# 5_ButtonsAndLEDs.net
KiCad netlist of a schematic drawn in Altium Designer
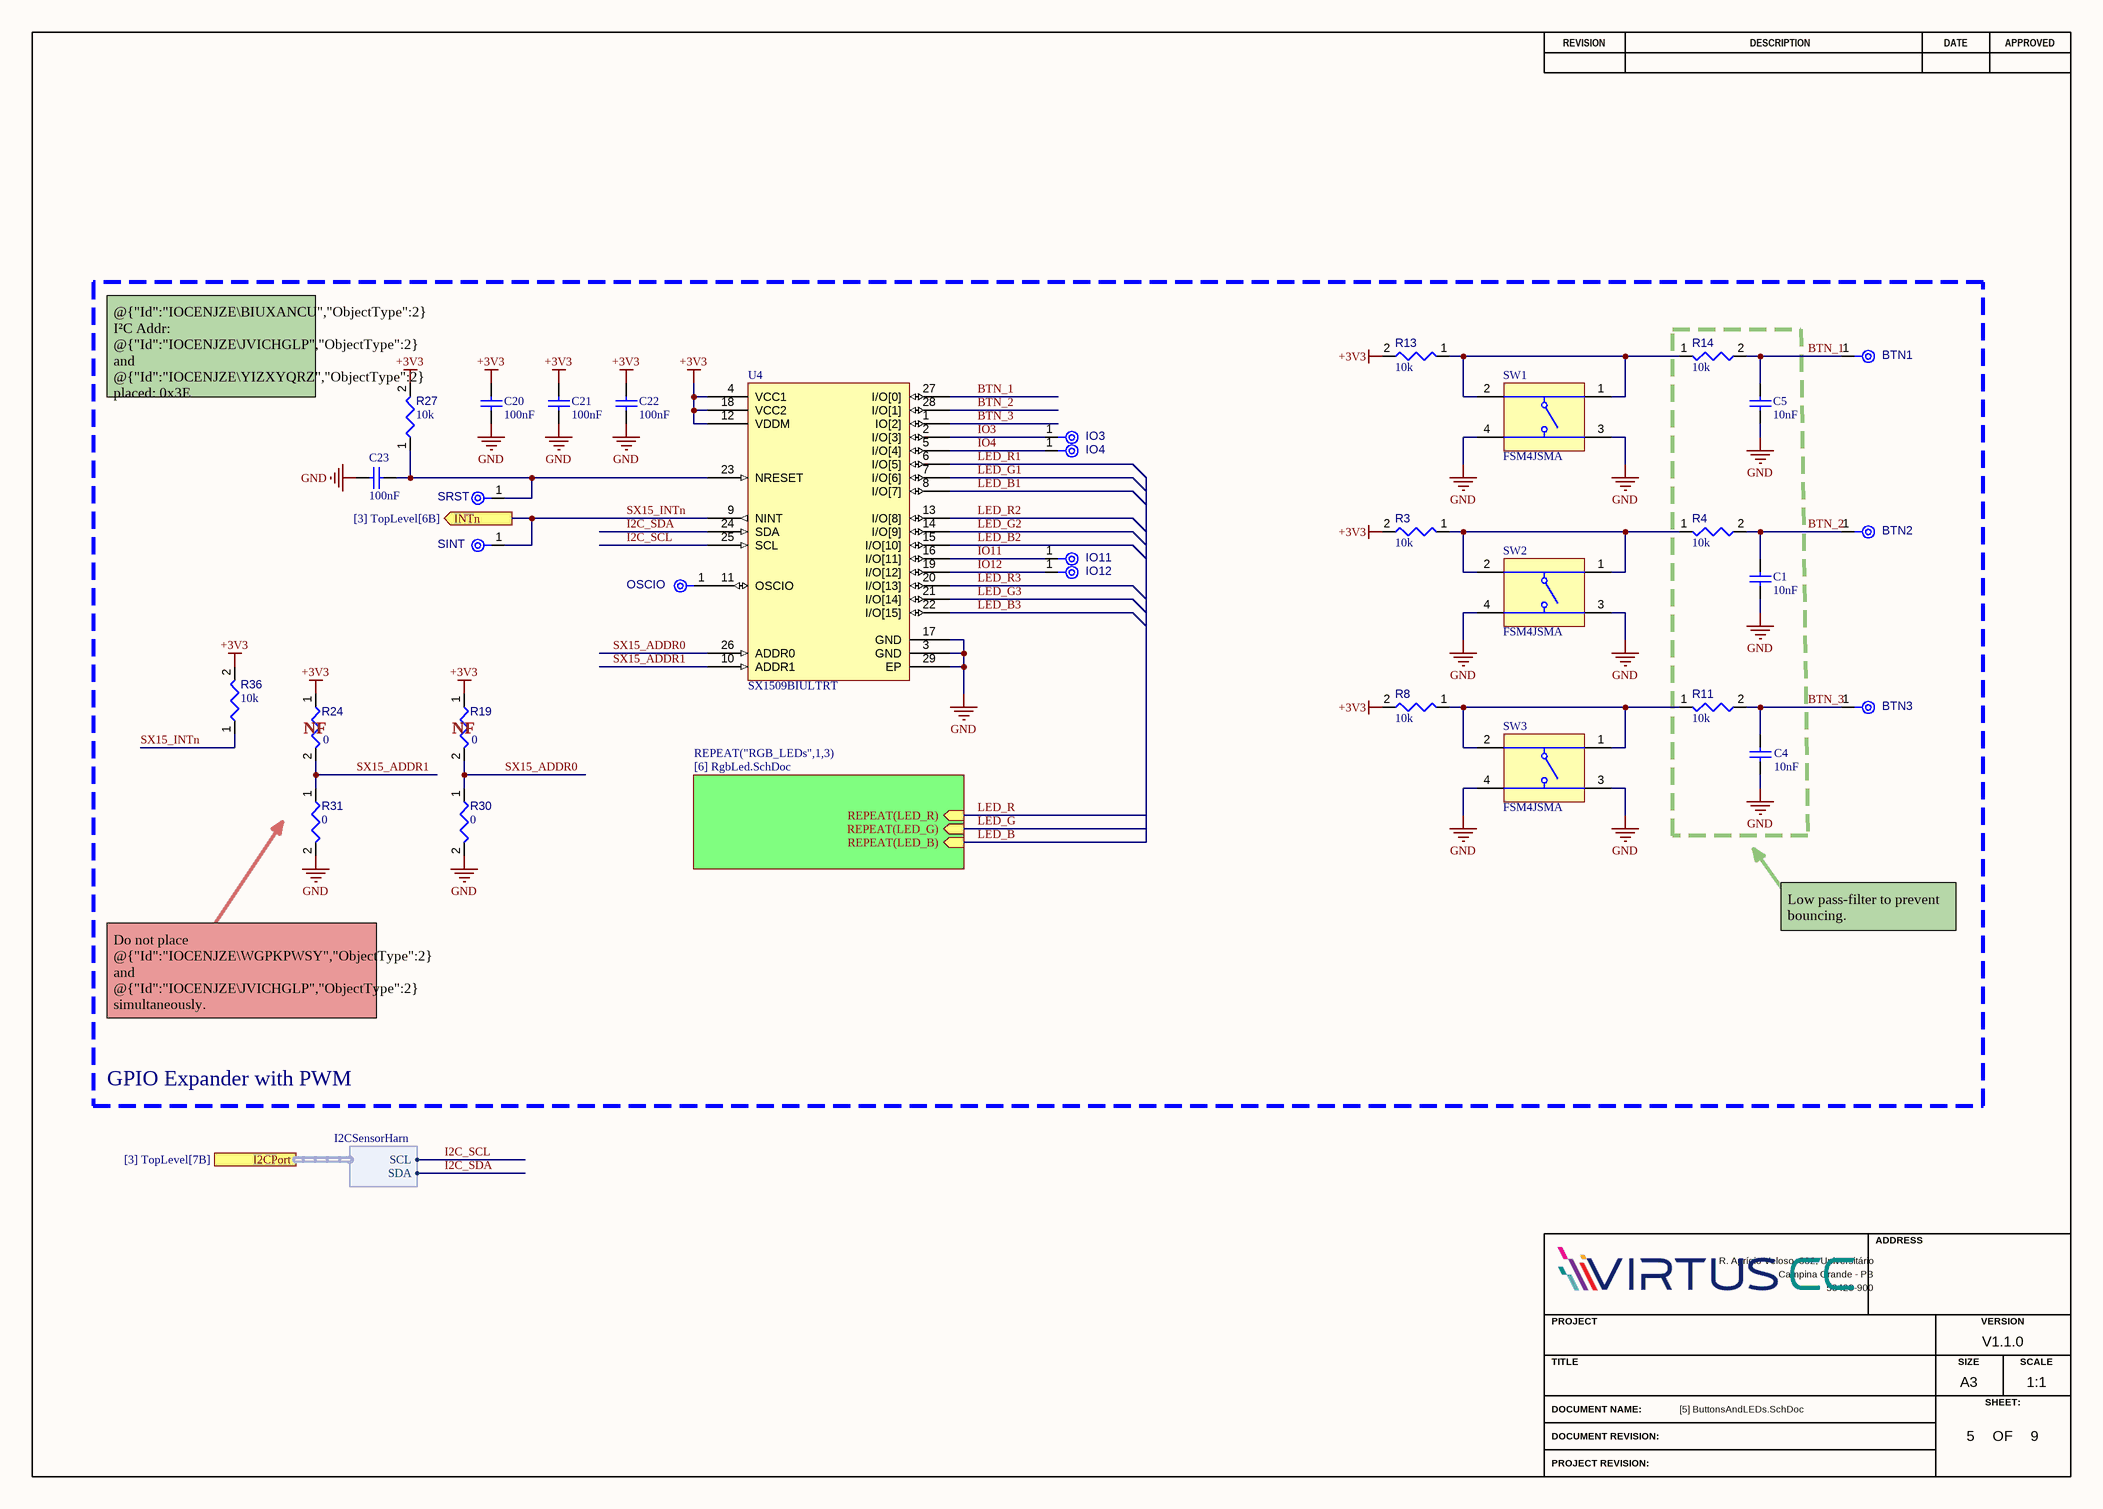
[diagram p0: [5] ButtonsAndLEDs.SchDoc]

(export (version "E")
  (design (tool "Eeschema 10.0.6"))
  (components
    (comp (ref "BTN1")
      (value "TPAD6R")
      (footprint "TP06R")
      (description "0.6mm round")
      (libsource (lib "UFCG - Universidade Federal de Campina Grande") (part "CMP-001-0001-4"))
    )
    (comp (ref "BTN2")
      (value "TPAD6R")
      (footprint "TP06R")
      (description "0.6mm round")
      (libsource (lib "UFCG - Universidade Federal de Campina Grande") (part "CMP-001-0001-4"))
    )
    (comp (ref "BTN3")
      (value "TPAD6R")
      (footprint "TP06R")
      (description "0.6mm round")
      (libsource (lib "UFCG - Universidade Federal de Campina Grande") (part "CMP-001-0001-4"))
    )
    (comp (ref "C1")
      (value "10nF")
      (footprint "CAPC0603(1608)100_L")
      (description "Multilayer Ceramic Capacitor, 0.01 uF, 50 V, ± 10%, X7R, 0603 [1608 Metric]")
      (fields (field (name "VOLTAGE") "50V") (field (name "TOLERANCE") "10%"))
      (libsource (lib "UFCG - Universidade Federal de Campina Grande") (part "CAP"))
    )
    (comp (ref "C4")
      (value "10nF")
      (footprint "CAPC0603(1608)100_L")
      (description "Multilayer Ceramic Capacitor, 0.01 uF, 50 V, ± 10%, X7R, 0603 [1608 Metric]")
      (fields (field (name "VOLTAGE") "50V") (field (name "TOLERANCE") "10%"))
      (libsource (lib "UFCG - Universidade Federal de Campina Grande") (part "CAP"))
    )
    (comp (ref "C5")
      (value "10nF")
      (footprint "CAPC0603(1608)100_L")
      (description "Multilayer Ceramic Capacitor, 0.01 uF, 50 V, ± 10%, X7R, 0603 [1608 Metric]")
      (fields (field (name "VOLTAGE") "50V") (field (name "TOLERANCE") "10%"))
      (libsource (lib "UFCG - Universidade Federal de Campina Grande") (part "CAP"))
    )
    (comp (ref "C20")
      (value "100nF")
      (footprint "CAPC0603(1608)100_L")
      (description "Multilayer Ceramic Capacitor, 0.1 uF, 16 V, ± 20%, X7R, 0603 [1608 Metric]")
      (fields (field (name "TOLERANCE") "20%") (field (name "Comment") "VJ0603Y104MXJCW1BC"))
      (libsource (lib "UFCG - Universidade Federal de Campina Grande") (part "CAP"))
    )
    (comp (ref "C21")
      (value "100nF")
      (footprint "CAPC0603(1608)100_L")
      (description "Multilayer Ceramic Capacitor, 0.1 uF, 16 V, ± 20%, X7R, 0603 [1608 Metric]")
      (fields (field (name "TOLERANCE") "20%") (field (name "Comment") "VJ0603Y104MXJCW1BC"))
      (libsource (lib "UFCG - Universidade Federal de Campina Grande") (part "CAP"))
    )
    (comp (ref "C22")
      (value "100nF")
      (footprint "CAPC0603(1608)100_L")
      (description "Multilayer Ceramic Capacitor, 0.1 uF, 16 V, ± 20%, X7R, 0603 [1608 Metric]")
      (fields (field (name "TOLERANCE") "20%") (field (name "Comment") "VJ0603Y104MXJCW1BC"))
      (libsource (lib "UFCG - Universidade Federal de Campina Grande") (part "CAP"))
    )
    (comp (ref "C23")
      (value "100nF")
      (footprint "CAPC0603(1608)100_L")
      (description "Multilayer Ceramic Capacitor, 0.1 uF, 16 V, ± 20%, X7R, 0603 [1608 Metric]")
      (fields (field (name "TOLERANCE") "20%") (field (name "Comment") "VJ0603Y104MXJCW1BC"))
      (libsource (lib "UFCG - Universidade Federal de Campina Grande") (part "CAP"))
    )
    (comp (ref "IO3")
      (value "TPAD6R")
      (footprint "TP06R")
      (description "0.6mm round")
      (libsource (lib "UFCG - Universidade Federal de Campina Grande") (part "CMP-001-0001-4"))
    )
    (comp (ref "IO4")
      (value "TPAD6R")
      (footprint "TP06R")
      (description "0.6mm round")
      (libsource (lib "UFCG - Universidade Federal de Campina Grande") (part "CMP-001-0001-4"))
    )
    (comp (ref "IO11")
      (value "TPAD6R")
      (footprint "TP06R")
      (description "0.6mm round")
      (libsource (lib "UFCG - Universidade Federal de Campina Grande") (part "CMP-001-0001-4"))
    )
    (comp (ref "IO12")
      (value "TPAD6R")
      (footprint "TP06R")
      (description "0.6mm round")
      (libsource (lib "UFCG - Universidade Federal de Campina Grande") (part "CMP-001-0001-4"))
    )
    (comp (ref "OSCIO")
      (value "TPAD6R")
      (footprint "TP06R")
      (description "0.6mm round")
      (libsource (lib "UFCG - Universidade Federal de Campina Grande") (part "CMP-001-0001-4"))
    )
    (comp (ref "R3")
      (value "10k")
      (footprint "RESC0603(1608)_L")
      (description "Chip Resistor, 10 KOhm, +/- 1%, 01 W, -55 to 155 degC, 0603 (1608 Metric)")
      (fields (field (name "POWER") "100mW") (field (name "TOLERANCE") "1%"))
      (libsource (lib "UFCG - Universidade Federal de Campina Grande") (part "RES-2"))
    )
    (comp (ref "R4")
      (value "10k")
      (footprint "RESC0603(1608)_L")
      (description "Chip Resistor, 10 KOhm, +/- 1%, 01 W, -55 to 155 degC, 0603 (1608 Metric)")
      (fields (field (name "POWER") "100mW") (field (name "TOLERANCE") "1%"))
      (libsource (lib "UFCG - Universidade Federal de Campina Grande") (part "RES-2"))
    )
    (comp (ref "R8")
      (value "10k")
      (footprint "RESC0603(1608)_L")
      (description "Chip Resistor, 10 KOhm, +/- 1%, 01 W, -55 to 155 degC, 0603 (1608 Metric)")
      (fields (field (name "POWER") "100mW") (field (name "TOLERANCE") "1%"))
      (libsource (lib "UFCG - Universidade Federal de Campina Grande") (part "RES-2"))
    )
    (comp (ref "R11")
      (value "10k")
      (footprint "RESC0603(1608)_L")
      (description "Chip Resistor, 10 KOhm, +/- 1%, 01 W, -55 to 155 degC, 0603 (1608 Metric)")
      (fields (field (name "POWER") "100mW") (field (name "TOLERANCE") "1%"))
      (libsource (lib "UFCG - Universidade Federal de Campina Grande") (part "RES-2"))
    )
    (comp (ref "R13")
      (value "10k")
      (footprint "RESC0603(1608)_L")
      (description "Chip Resistor, 10 KOhm, +/- 1%, 01 W, -55 to 155 degC, 0603 (1608 Metric)")
      (fields (field (name "POWER") "100mW") (field (name "TOLERANCE") "1%"))
      (libsource (lib "UFCG - Universidade Federal de Campina Grande") (part "RES-2"))
    )
    (comp (ref "R14")
      (value "10k")
      (footprint "RESC0603(1608)_L")
      (description "Chip Resistor, 10 KOhm, +/- 1%, 01 W, -55 to 155 degC, 0603 (1608 Metric)")
      (fields (field (name "POWER") "100mW") (field (name "TOLERANCE") "1%"))
      (libsource (lib "UFCG - Universidade Federal de Campina Grande") (part "RES-2"))
    )
    (comp (ref "R19")
      (value "0")
      (footprint "RESC0603(1608)_L")
      (description "Chip Resistor, 0 Ohm, 0.1 W, -55 to 155 degC, 0603 (1608 Metric)")
      (fields (field (name "TOLERANCE") "5%") (field (name "POWER") "100mW"))
      (libsource (lib "UFCG - Universidade Federal de Campina Grande") (part "RES-2"))
    )
    (comp (ref "R24")
      (value "0")
      (footprint "RESC0603(1608)_L")
      (description "Chip Resistor, 0 Ohm, 0.1 W, -55 to 155 degC, 0603 (1608 Metric)")
      (fields (field (name "TOLERANCE") "5%") (field (name "POWER") "100mW"))
      (libsource (lib "UFCG - Universidade Federal de Campina Grande") (part "RES-2"))
    )
    (comp (ref "R27")
      (value "10k")
      (footprint "RESC0603(1608)_L")
      (description "Chip Resistor, 10 KOhm, +/- 1%, 01 W, -55 to 155 degC, 0603 (1608 Metric)")
      (fields (field (name "POWER") "100mW") (field (name "TOLERANCE") "1%"))
      (libsource (lib "UFCG - Universidade Federal de Campina Grande") (part "RES-2"))
    )
    (comp (ref "R30")
      (value "0")
      (footprint "RESC0603(1608)_L")
      (description "Chip Resistor, 0 Ohm, 0.1 W, -55 to 155 degC, 0603 (1608 Metric)")
      (fields (field (name "TOLERANCE") "5%") (field (name "POWER") "100mW"))
      (libsource (lib "UFCG - Universidade Federal de Campina Grande") (part "RES-2"))
    )
    (comp (ref "R31")
      (value "0")
      (footprint "RESC0603(1608)_L")
      (description "Chip Resistor, 0 Ohm, 0.1 W, -55 to 155 degC, 0603 (1608 Metric)")
      (fields (field (name "TOLERANCE") "5%") (field (name "POWER") "100mW"))
      (libsource (lib "UFCG - Universidade Federal de Campina Grande") (part "RES-2"))
    )
    (comp (ref "R36")
      (value "10k")
      (footprint "RESC0603(1608)_L")
      (description "Chip Resistor, 10 KOhm, +/- 1%, 01 W, -55 to 155 degC, 0603 (1608 Metric)")
      (fields (field (name "POWER") "100mW") (field (name "TOLERANCE") "1%"))
      (libsource (lib "UFCG - Universidade Federal de Campina Grande") (part "RES-2"))
    )
    (comp (ref "SINT")
      (value "TPAD6R")
      (footprint "TP06R")
      (description "0.6mm round")
      (libsource (lib "UFCG - Universidade Federal de Campina Grande") (part "CMP-001-0001-4"))
    )
    (comp (ref "SRST")
      (value "TPAD6R")
      (footprint "TP06R")
      (description "0.6mm round")
      (libsource (lib "UFCG - Universidade Federal de Campina Grande") (part "CMP-001-0001-4"))
    )
    (comp (ref "SW1")
      (value "FSM4JSMA")
      (footprint "TECO-FSM4JSMA_V")
      (description "Switch Tactile OFF (ON) SPST Round Button Gull Wing 0.05A 12VDC 1.57N SMD Loose Piece")
      (libsource (lib "UFCG - Universidade Federal de Campina Grande") (part "SW-SPST-4_A"))
    )
    (comp (ref "SW2")
      (value "FSM4JSMA")
      (footprint "TECO-FSM4JSMA_V")
      (description "Switch Tactile OFF (ON) SPST Round Button Gull Wing 0.05A 12VDC 1.57N SMD Loose Piece")
      (libsource (lib "UFCG - Universidade Federal de Campina Grande") (part "SW-SPST-4_A"))
    )
    (comp (ref "SW3")
      (value "FSM4JSMA")
      (footprint "TECO-FSM4JSMA_V")
      (description "Switch Tactile OFF (ON) SPST Round Button Gull Wing 0.05A 12VDC 1.57N SMD Loose Piece")
      (libsource (lib "UFCG - Universidade Federal de Campina Grande") (part "SW-SPST-4_A"))
    )
    (comp (ref "U4")
      (value "SX1509BIULTRT")
      (footprint "QFN40P410X410X60_HS-29N")
      (description "IC Gpio Expander I2C 16CH 28QFN / I2C Interface 5.5V 28-PIN Qfn-ut Ep T/r")
      (libsource (lib "UFCG - Universidade Federal de Campina Grande") (part "New symbol 1"))
    )
  )
  (nets
    (net (code "2") (name "+3V3") (class "Default")
      (node (ref "C20") (pin "1") (pinfunction "1_1") (pintype "passive"))
      (node (ref "C21") (pin "1") (pinfunction "1_1") (pintype "passive"))
      (node (ref "C22") (pin "1") (pinfunction "1_1") (pintype "passive"))
      (node (ref "R13") (pin "2") (pinfunction "2_2") (pintype "passive"))
      (node (ref "R19") (pin "1") (pinfunction "1_1") (pintype "passive"))
      (node (ref "R24") (pin "1") (pinfunction "1_1") (pintype "passive"))
      (node (ref "R27") (pin "2") (pinfunction "2_2") (pintype "passive"))
      (node (ref "R3") (pin "2") (pinfunction "2_2") (pintype "passive"))
      (node (ref "R36") (pin "2") (pinfunction "2_2") (pintype "passive"))
      (node (ref "R8") (pin "2") (pinfunction "2_2") (pintype "passive"))
      (node (ref "U4") (pin "12") (pinfunction "VDDM_12") (pintype "power_in"))
      (node (ref "U4") (pin "18") (pinfunction "VCC2_18") (pintype "power_in"))
      (node (ref "U4") (pin "4") (pinfunction "VCC1_4") (pintype "power_in"))
    )
    (net (code "3") (name "/BTN_1") (class "Default")
      (node (ref "BTN1") (pin "1") (pinfunction "TP_1") (pintype "passive"))
      (node (ref "C5") (pin "2") (pinfunction "2_2") (pintype "passive"))
      (node (ref "R14") (pin "2") (pinfunction "2_2") (pintype "passive"))
      (node (ref "U4") (pin "27") (pinfunction "I/O[0]_27") (pintype "bidirectional"))
    )
    (net (code "4") (name "/BTN_2") (class "Default")
      (node (ref "BTN2") (pin "1") (pinfunction "TP_1") (pintype "passive"))
      (node (ref "C1") (pin "2") (pinfunction "2_2") (pintype "passive"))
      (node (ref "R4") (pin "2") (pinfunction "2_2") (pintype "passive"))
      (node (ref "U4") (pin "28") (pinfunction "I/O[1]_28") (pintype "bidirectional"))
    )
    (net (code "5") (name "/BTN_3") (class "Default")
      (node (ref "BTN3") (pin "1") (pinfunction "TP_1") (pintype "passive"))
      (node (ref "C4") (pin "2") (pinfunction "2_2") (pintype "passive"))
      (node (ref "R11") (pin "2") (pinfunction "2_2") (pintype "passive"))
      (node (ref "U4") (pin "1") (pinfunction "IO[2]_1") (pintype "bidirectional"))
    )
    (net (code "6") (name "/I2C_SCL") (class "Default")
      (node (ref "U4") (pin "25") (pinfunction "SCL_25") (pintype "input"))
    )
    (net (code "7") (name "/I2C_SDA") (class "Default")
      (node (ref "U4") (pin "24") (pinfunction "SDA_24") (pintype "input"))
    )
    (net (code "8") (name "/IO3") (class "Default")
      (node (ref "IO3") (pin "1") (pinfunction "TP_1") (pintype "passive"))
      (node (ref "U4") (pin "2") (pinfunction "I/O[3]_2") (pintype "bidirectional"))
    )
    (net (code "9") (name "/IO4") (class "Default")
      (node (ref "IO4") (pin "1") (pinfunction "TP_1") (pintype "passive"))
      (node (ref "U4") (pin "5") (pinfunction "I/O[4]_5") (pintype "bidirectional"))
    )
    (net (code "10") (name "/IO11") (class "Default")
      (node (ref "IO11") (pin "1") (pinfunction "TP_1") (pintype "passive"))
      (node (ref "U4") (pin "16") (pinfunction "I/O[11]_16") (pintype "bidirectional"))
    )
    (net (code "11") (name "/IO12") (class "Default")
      (node (ref "IO12") (pin "1") (pinfunction "TP_1") (pintype "passive"))
      (node (ref "U4") (pin "19") (pinfunction "I/O[12]_19") (pintype "bidirectional"))
    )
    (net (code "13") (name "/LED_B1") (class "Default")
      (node (ref "U4") (pin "8") (pinfunction "I/O[7]_8") (pintype "bidirectional"))
    )
    (net (code "14") (name "/LED_B2") (class "Default")
      (node (ref "U4") (pin "15") (pinfunction "I/O[10]_15") (pintype "bidirectional"))
    )
    (net (code "15") (name "/LED_B3") (class "Default")
      (node (ref "U4") (pin "22") (pinfunction "I/O[15]_22") (pintype "bidirectional"))
    )
    (net (code "17") (name "/LED_G1") (class "Default")
      (node (ref "U4") (pin "7") (pinfunction "I/O[6]_7") (pintype "bidirectional"))
    )
    (net (code "18") (name "/LED_G2") (class "Default")
      (node (ref "U4") (pin "14") (pinfunction "I/O[9]_14") (pintype "bidirectional"))
    )
    (net (code "19") (name "/LED_G3") (class "Default")
      (node (ref "U4") (pin "21") (pinfunction "I/O[14]_21") (pintype "bidirectional"))
    )
    (net (code "21") (name "/LED_R1") (class "Default")
      (node (ref "U4") (pin "6") (pinfunction "I/O[5]_6") (pintype "bidirectional"))
    )
    (net (code "22") (name "/LED_R2") (class "Default")
      (node (ref "U4") (pin "13") (pinfunction "I/O[8]_13") (pintype "bidirectional"))
    )
    (net (code "23") (name "/LED_R3") (class "Default")
      (node (ref "U4") (pin "20") (pinfunction "I/O[13]_20") (pintype "bidirectional"))
    )
    (net (code "24") (name "/SX15_ADDR0") (class "Default")
      (node (ref "R19") (pin "2") (pinfunction "2_2") (pintype "passive"))
      (node (ref "R30") (pin "1") (pinfunction "1_1") (pintype "passive"))
      (node (ref "U4") (pin "26") (pinfunction "ADDR0_26") (pintype "input"))
    )
    (net (code "25") (name "/SX15_ADDR1") (class "Default")
      (node (ref "R24") (pin "2") (pinfunction "2_2") (pintype "passive"))
      (node (ref "R31") (pin "1") (pinfunction "1_1") (pintype "passive"))
      (node (ref "U4") (pin "10") (pinfunction "ADDR1_10") (pintype "input"))
    )
    (net (code "26") (name "/SX15_INTn") (class "Default")
      (node (ref "R36") (pin "1") (pinfunction "1_1") (pintype "passive"))
      (node (ref "SINT") (pin "1") (pinfunction "TP_1") (pintype "passive"))
      (node (ref "U4") (pin "9") (pinfunction "NINT_9") (pintype "output"))
    )
    (net (code "28") (name "GND") (class "Default")
      (node (ref "C1") (pin "1") (pinfunction "1_1") (pintype "passive"))
      (node (ref "C20") (pin "2") (pinfunction "2_2") (pintype "passive"))
      (node (ref "C21") (pin "2") (pinfunction "2_2") (pintype "passive"))
      (node (ref "C22") (pin "2") (pinfunction "2_2") (pintype "passive"))
      (node (ref "C23") (pin "2") (pinfunction "2_2") (pintype "passive"))
      (node (ref "C4") (pin "1") (pinfunction "1_1") (pintype "passive"))
      (node (ref "C5") (pin "1") (pinfunction "1_1") (pintype "passive"))
      (node (ref "R30") (pin "2") (pinfunction "2_2") (pintype "passive"))
      (node (ref "R31") (pin "2") (pinfunction "2_2") (pintype "passive"))
      (node (ref "SW1") (pin "3") (pinfunction "3_3") (pintype "passive"))
      (node (ref "SW1") (pin "4") (pinfunction "4_4") (pintype "passive"))
      (node (ref "SW2") (pin "3") (pinfunction "3_3") (pintype "passive"))
      (node (ref "SW2") (pin "4") (pinfunction "4_4") (pintype "passive"))
      (node (ref "SW3") (pin "3") (pinfunction "3_3") (pintype "passive"))
      (node (ref "SW3") (pin "4") (pinfunction "4_4") (pintype "passive"))
      (node (ref "U4") (pin "17") (pinfunction "GND_17") (pintype "power_in"))
      (node (ref "U4") (pin "29") (pinfunction "EP_29") (pintype "power_in"))
      (node (ref "U4") (pin "3") (pinfunction "GND_3") (pintype "power_in"))
    )
    (net (code "29") (name "Net-(OSCIO-TP)") (class "Default")
      (node (ref "OSCIO") (pin "1") (pinfunction "TP_1") (pintype "passive"))
      (node (ref "U4") (pin "11") (pinfunction "OSCIO_11") (pintype "bidirectional"))
    )
    (net (code "30") (name "Net-(R3-Pad1)") (class "Default")
      (node (ref "R3") (pin "1") (pinfunction "1_1") (pintype "passive"))
      (node (ref "R4") (pin "1") (pinfunction "1_1") (pintype "passive"))
      (node (ref "SW2") (pin "1") (pinfunction "1_1") (pintype "passive"))
      (node (ref "SW2") (pin "2") (pinfunction "2_2") (pintype "passive"))
    )
    (net (code "31") (name "Net-(R11-Pad1)") (class "Default")
      (node (ref "R11") (pin "1") (pinfunction "1_1") (pintype "passive"))
      (node (ref "R8") (pin "1") (pinfunction "1_1") (pintype "passive"))
      (node (ref "SW3") (pin "1") (pinfunction "1_1") (pintype "passive"))
      (node (ref "SW3") (pin "2") (pinfunction "2_2") (pintype "passive"))
    )
    (net (code "32") (name "Net-(R13-Pad1)") (class "Default")
      (node (ref "R13") (pin "1") (pinfunction "1_1") (pintype "passive"))
      (node (ref "R14") (pin "1") (pinfunction "1_1") (pintype "passive"))
      (node (ref "SW1") (pin "1") (pinfunction "1_1") (pintype "passive"))
      (node (ref "SW1") (pin "2") (pinfunction "2_2") (pintype "passive"))
    )
    (net (code "33") (name "Net-(SRST-TP)") (class "Default")
      (node (ref "C23") (pin "1") (pinfunction "1_1") (pintype "passive"))
      (node (ref "R27") (pin "1") (pinfunction "1_1") (pintype "passive"))
      (node (ref "SRST") (pin "1") (pinfunction "TP_1") (pintype "passive"))
      (node (ref "U4") (pin "23") (pinfunction "NRESET_23") (pintype "input"))
    )
  )
)
